# esp8285_v01.net
KiCad netlist of a schematic drawn in EAGLE
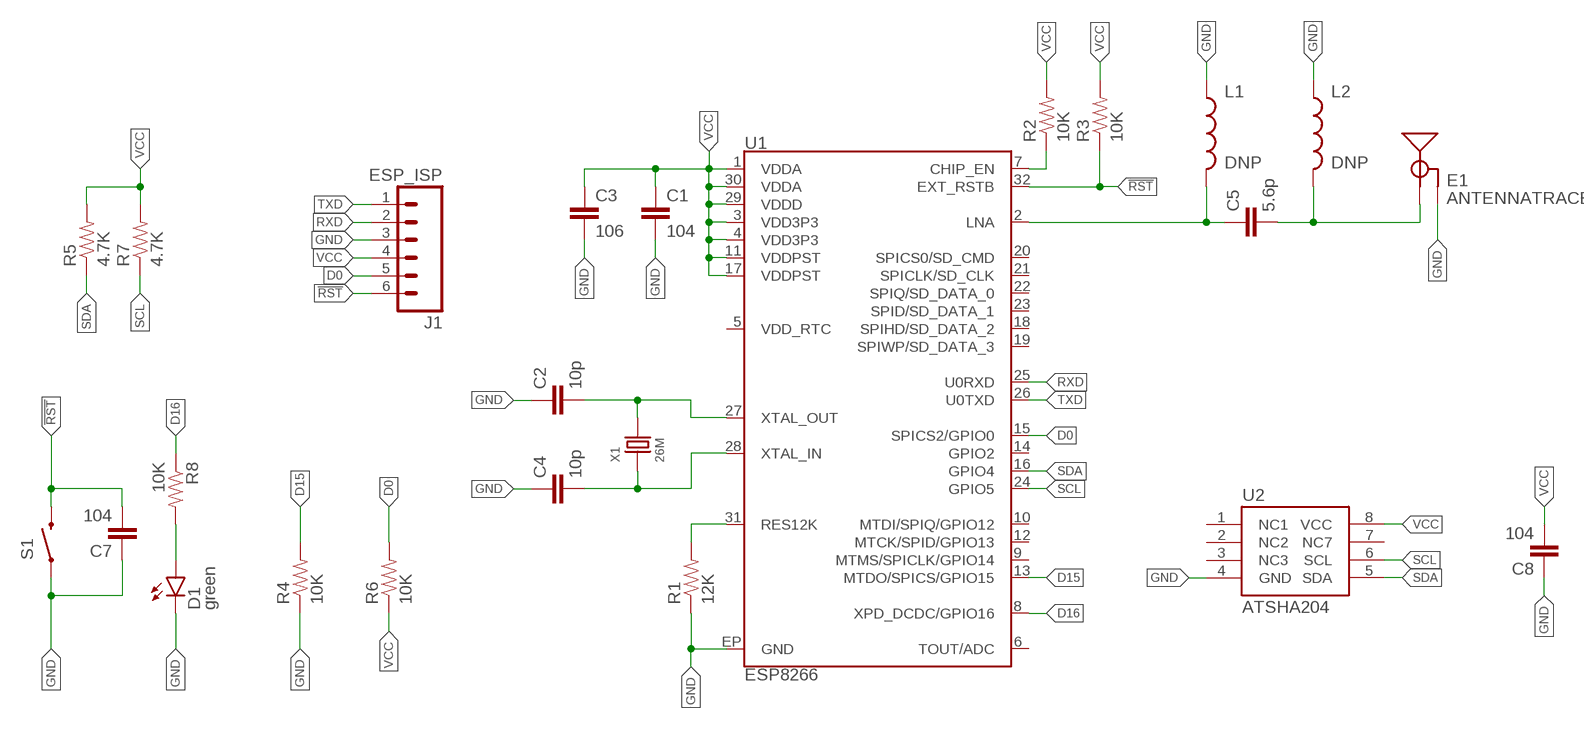
[diagram p0: schematic, sheet 1]

(export (version "E")
  (design (tool "Eeschema 10.0.6"))
  (components
    (comp (ref "C1")
      (value "104")
      (footprint "eagle-import:0402-CAP")
      (libsource (lib "eagle-import") (part "CAP0402-CAP"))
    )
    (comp (ref "C2")
      (value "10p")
      (footprint "eagle-import:0402-CAP")
      (libsource (lib "eagle-import") (part "CAP0402-CAP"))
    )
    (comp (ref "C3")
      (value "106")
      (footprint "eagle-import:0402-CAP")
      (libsource (lib "eagle-import") (part "CAP0402-CAP"))
    )
    (comp (ref "C4")
      (value "10p")
      (footprint "eagle-import:0402-CAP")
      (libsource (lib "eagle-import") (part "CAP0402-CAP"))
    )
    (comp (ref "C5")
      (value "5.6p")
      (footprint "eagle-import:0402-CAP")
      (libsource (lib "eagle-import") (part "CAP0402-CAP"))
    )
    (comp (ref "C7")
      (value "104")
      (footprint "eagle-import:0402-CAP")
      (libsource (lib "eagle-import") (part "CAP0402-CAP"))
    )
    (comp (ref "C8")
      (value "104")
      (footprint "eagle-import:0402-CAP")
      (libsource (lib "eagle-import") (part "CAP0402-CAP"))
    )
    (comp (ref "D1")
      (value "green")
      (footprint "eagle-import:LED-0603-EASY")
      (libsource (lib "eagle-import") (part "LED-EASY"))
    )
    (comp (ref "E1")
      (value "ANTENNATRACE")
      (footprint "eagle-import:TRACE_ANTENNA_2.4GHZ_25.7MM")
      (libsource (lib "eagle-import") (part "ANTENNATRACE"))
    )
    (comp (ref "J1")
      (value "ESP_ISP")
      (footprint "eagle-import:1X06_NO_SILK")
      (libsource (lib "eagle-import") (part "M06NO_SILK_FEMALE_PTH"))
    )
    (comp (ref "L1")
      (value "DNP")
      (footprint "eagle-import:C0402")
      (libsource (lib "eagle-import") (part "INDUCTOR0402"))
    )
    (comp (ref "L2")
      (value "DNP")
      (footprint "eagle-import:C0402")
      (libsource (lib "eagle-import") (part "INDUCTOR0402"))
    )
    (comp (ref "R1")
      (value "12K")
      (footprint "eagle-import:0402-RES")
      (libsource (lib "eagle-import") (part "RESISTOR0402"))
    )
    (comp (ref "R2")
      (value "10K")
      (footprint "eagle-import:0402-RES")
      (libsource (lib "eagle-import") (part "RESISTOR0402"))
    )
    (comp (ref "R3")
      (value "10K")
      (footprint "eagle-import:0402-RES")
      (libsource (lib "eagle-import") (part "RESISTOR0402"))
    )
    (comp (ref "R4")
      (value "10K")
      (footprint "eagle-import:0402-RES")
      (libsource (lib "eagle-import") (part "RESISTOR0402"))
    )
    (comp (ref "R5")
      (value "4.7K")
      (footprint "eagle-import:0402-RES")
      (libsource (lib "eagle-import") (part "RESISTOR0402"))
    )
    (comp (ref "R6")
      (value "10K")
      (footprint "eagle-import:0402-RES")
      (libsource (lib "eagle-import") (part "RESISTOR0402"))
    )
    (comp (ref "R7")
      (value "4.7K")
      (footprint "eagle-import:0402-RES")
      (libsource (lib "eagle-import") (part "RESISTOR0402"))
    )
    (comp (ref "R8")
      (value "10K")
      (footprint "eagle-import:0402-RES")
      (libsource (lib "eagle-import") (part "RESISTOR0402"))
    )
    (comp (ref "S1")
      (value "SWITCH-MOMENTARY-2SMD-1101NE")
      (footprint "eagle-import:TACTILE-SWITCH-1101NE")
      (libsource (lib "eagle-import") (part "SWITCH-MOMENTARY-2SMD-1101NE"))
    )
    (comp (ref "U1")
      (value "ESP8266")
      (footprint "eagle-import:QFN32")
      (libsource (lib "eagle-import") (part "ESP8266"))
    )
    (comp (ref "U2")
      (value "ATSHA204")
      (footprint "eagle-import:SO08")
      (libsource (lib "eagle-import") (part "ATSHA204_SOIC8"))
    )
    (comp (ref "X1")
      (value "26M")
      (footprint "eagle-import:X4-SMD-3.2X2.5X0.7MM")
      (libsource (lib "eagle-import") (part "CRYSTAL'3225'"))
    )
  )
  (nets
    (net (code "1") (name "/~{RST}") (class "Default")
      (node (ref "C7") (pin "2") (pinfunction "2_2") (pintype "passive"))
      (node (ref "J1") (pin "6") (pinfunction "6_6") (pintype "passive"))
      (node (ref "R3") (pin "1") (pinfunction "1_1") (pintype "passive"))
      (node (ref "S1") (pin "2") (pinfunction "2_2") (pintype "passive"))
      (node (ref "U1") (pin "32") (pinfunction "EXT_RSTB_32") (pintype "bidirectional"))
    )
    (net (code "2") (name "D0") (class "Default")
      (node (ref "J1") (pin "5") (pinfunction "5_5") (pintype "passive"))
      (node (ref "R6") (pin "2") (pinfunction "2_2") (pintype "passive"))
      (node (ref "U1") (pin "15") (pinfunction "SPICS2/GPIO0_15") (pintype "bidirectional"))
    )
    (net (code "3") (name "D15") (class "Default")
      (node (ref "R4") (pin "2") (pinfunction "2_2") (pintype "passive"))
      (node (ref "U1") (pin "13") (pinfunction "MTDO/SPICS/GPIO15_13") (pintype "bidirectional"))
    )
    (net (code "4") (name "D16") (class "Default")
      (node (ref "R8") (pin "1") (pinfunction "1_1") (pintype "passive"))
      (node (ref "U1") (pin "8") (pinfunction "XPD_DCDC/GPIO16_8") (pintype "bidirectional"))
    )
    (net (code "5") (name "GND") (class "Default")
      (node (ref "C1") (pin "2") (pinfunction "2_2") (pintype "passive"))
      (node (ref "C2") (pin "1") (pinfunction "1_1") (pintype "passive"))
      (node (ref "C3") (pin "2") (pinfunction "2_2") (pintype "passive"))
      (node (ref "C4") (pin "1") (pinfunction "1_1") (pintype "passive"))
      (node (ref "C7") (pin "1") (pinfunction "1_1") (pintype "passive"))
      (node (ref "C8") (pin "1") (pinfunction "1_1") (pintype "passive"))
      (node (ref "D1") (pin "-") (pinfunction "C_-") (pintype "passive"))
      (node (ref "E1") (pin "GND") (pinfunction "GND_GND") (pintype "bidirectional"))
      (node (ref "E1") (pin "GND2") (pinfunction "GND_GND2") (pintype "bidirectional"))
      (node (ref "J1") (pin "3") (pinfunction "3_3") (pintype "passive"))
      (node (ref "L1") (pin "1") (pinfunction "1_1") (pintype "passive"))
      (node (ref "L2") (pin "1") (pinfunction "1_1") (pintype "passive"))
      (node (ref "R1") (pin "1") (pinfunction "1_1") (pintype "passive"))
      (node (ref "R4") (pin "1") (pinfunction "1_1") (pintype "passive"))
      (node (ref "S1") (pin "1") (pinfunction "1_1") (pintype "passive"))
      (node (ref "U1") (pin "EP") (pinfunction "GND_EP") (pintype "bidirectional"))
      (node (ref "U2") (pin "4") (pinfunction "GND_4") (pintype "power_in"))
    )
    (net (code "6") (name "Net-(D1-A)") (class "Default")
      (node (ref "D1") (pin "+") (pinfunction "A_+") (pintype "passive"))
      (node (ref "R8") (pin "2") (pinfunction "2_2") (pintype "passive"))
    )
    (net (code "7") (name "Net-(E1-SIGNAL)") (class "Default")
      (node (ref "C5") (pin "2") (pinfunction "2_2") (pintype "passive"))
      (node (ref "E1") (pin "ANT") (pinfunction "SIGNAL_ANT") (pintype "bidirectional"))
      (node (ref "L2") (pin "2") (pinfunction "2_2") (pintype "passive"))
    )
    (net (code "8") (name "Net-(U1-CHIP_EN)") (class "Default")
      (node (ref "R2") (pin "1") (pinfunction "1_1") (pintype "passive"))
      (node (ref "U1") (pin "7") (pinfunction "CHIP_EN_7") (pintype "bidirectional"))
    )
    (net (code "9") (name "Net-(U1-LNA)") (class "Default")
      (node (ref "C5") (pin "1") (pinfunction "1_1") (pintype "passive"))
      (node (ref "L1") (pin "2") (pinfunction "2_2") (pintype "passive"))
      (node (ref "U1") (pin "2") (pinfunction "LNA_2") (pintype "bidirectional"))
    )
    (net (code "10") (name "Net-(U1-RES12K)") (class "Default")
      (node (ref "R1") (pin "2") (pinfunction "2_2") (pintype "passive"))
      (node (ref "U1") (pin "31") (pinfunction "RES12K_31") (pintype "bidirectional"))
    )
    (net (code "11") (name "Net-(U1-XTAL_IN)") (class "Default")
      (node (ref "C4") (pin "2") (pinfunction "2_2") (pintype "passive"))
      (node (ref "U1") (pin "28") (pinfunction "XTAL_IN_28") (pintype "bidirectional"))
      (node (ref "X1") (pin "1") (pinfunction "1_1") (pintype "passive"))
    )
    (net (code "12") (name "Net-(U1-XTAL_OUT)") (class "Default")
      (node (ref "C2") (pin "2") (pinfunction "2_2") (pintype "passive"))
      (node (ref "U1") (pin "27") (pinfunction "XTAL_OUT_27") (pintype "bidirectional"))
      (node (ref "X1") (pin "3") (pinfunction "2_3") (pintype "passive"))
    )
    (net (code "13") (name "RXD") (class "Default")
      (node (ref "J1") (pin "2") (pinfunction "2_2") (pintype "passive"))
      (node (ref "U1") (pin "25") (pinfunction "U0RXD_25") (pintype "bidirectional"))
    )
    (net (code "14") (name "SCL") (class "Default")
      (node (ref "R7") (pin "1") (pinfunction "1_1") (pintype "passive"))
      (node (ref "U1") (pin "24") (pinfunction "GPIO5_24") (pintype "bidirectional"))
      (node (ref "U2") (pin "6") (pinfunction "SCL_6") (pintype "bidirectional"))
    )
    (net (code "15") (name "SDA") (class "Default")
      (node (ref "R5") (pin "1") (pinfunction "1_1") (pintype "passive"))
      (node (ref "U1") (pin "16") (pinfunction "GPIO4_16") (pintype "bidirectional"))
      (node (ref "U2") (pin "5") (pinfunction "SDA_5") (pintype "bidirectional"))
    )
    (net (code "16") (name "TXD") (class "Default")
      (node (ref "J1") (pin "1") (pinfunction "1_1") (pintype "passive"))
      (node (ref "U1") (pin "26") (pinfunction "U0TXD_26") (pintype "bidirectional"))
    )
    (net (code "17") (name "VCC") (class "Default")
      (node (ref "C1") (pin "1") (pinfunction "1_1") (pintype "passive"))
      (node (ref "C3") (pin "1") (pinfunction "1_1") (pintype "passive"))
      (node (ref "C8") (pin "2") (pinfunction "2_2") (pintype "passive"))
      (node (ref "J1") (pin "4") (pinfunction "4_4") (pintype "passive"))
      (node (ref "R2") (pin "2") (pinfunction "2_2") (pintype "passive"))
      (node (ref "R3") (pin "2") (pinfunction "2_2") (pintype "passive"))
      (node (ref "R5") (pin "2") (pinfunction "2_2") (pintype "passive"))
      (node (ref "R6") (pin "1") (pinfunction "1_1") (pintype "passive"))
      (node (ref "R7") (pin "2") (pinfunction "2_2") (pintype "passive"))
      (node (ref "U1") (pin "1") (pinfunction "VDDA_1") (pintype "bidirectional"))
      (node (ref "U1") (pin "11") (pinfunction "VDDPST_11") (pintype "bidirectional"))
      (node (ref "U1") (pin "17") (pinfunction "VDDPST_17") (pintype "bidirectional"))
      (node (ref "U1") (pin "29") (pinfunction "VDDD_29") (pintype "bidirectional"))
      (node (ref "U1") (pin "3") (pinfunction "VDD3P3_3") (pintype "bidirectional"))
      (node (ref "U1") (pin "30") (pinfunction "VDDA_30") (pintype "bidirectional"))
      (node (ref "U1") (pin "4") (pinfunction "VDD3P3_4") (pintype "bidirectional"))
      (node (ref "U2") (pin "8") (pinfunction "VCC_8") (pintype "power_in"))
    )
    (net (code "18") (name "unconnected-(U1-GPIO2-Pad14)") (class "Default")
      (node (ref "U1") (pin "14") (pinfunction "GPIO2_14") (pintype "bidirectional"))
    )
    (net (code "19") (name "unconnected-(U1-MTCK{slash}SPID{slash}GPIO13-Pad12)") (class "Default")
      (node (ref "U1") (pin "12") (pinfunction "MTCK/SPID/GPIO13_12") (pintype "bidirectional"))
    )
    (net (code "20") (name "unconnected-(U1-MTDI{slash}SPIQ{slash}GPIO12-Pad10)") (class "Default")
      (node (ref "U1") (pin "10") (pinfunction "MTDI/SPIQ/GPIO12_10") (pintype "bidirectional"))
    )
    (net (code "21") (name "unconnected-(U1-MTMS{slash}SPICLK{slash}GPIO14-Pad9)") (class "Default")
      (node (ref "U1") (pin "9") (pinfunction "MTMS/SPICLK/GPIO14_9") (pintype "bidirectional"))
    )
    (net (code "22") (name "unconnected-(U1-SPICLK{slash}SD_CLK-Pad21)") (class "Default")
      (node (ref "U1") (pin "21") (pinfunction "SPICLK/SD_CLK_21") (pintype "bidirectional"))
    )
    (net (code "23") (name "unconnected-(U1-SPICS0{slash}SD_CMD-Pad20)") (class "Default")
      (node (ref "U1") (pin "20") (pinfunction "SPICS0/SD_CMD_20") (pintype "bidirectional"))
    )
    (net (code "24") (name "unconnected-(U1-SPID{slash}SD_DATA_1-Pad23)") (class "Default")
      (node (ref "U1") (pin "23") (pinfunction "SPID/SD_DATA_1_23") (pintype "bidirectional"))
    )
    (net (code "25") (name "unconnected-(U1-SPIHD{slash}SD_DATA_2-Pad18)") (class "Default")
      (node (ref "U1") (pin "18") (pinfunction "SPIHD/SD_DATA_2_18") (pintype "bidirectional"))
    )
    (net (code "26") (name "unconnected-(U1-SPIQ{slash}SD_DATA_0-Pad22)") (class "Default")
      (node (ref "U1") (pin "22") (pinfunction "SPIQ/SD_DATA_0_22") (pintype "bidirectional"))
    )
    (net (code "27") (name "unconnected-(U1-SPIWP{slash}SD_DATA_3-Pad19)") (class "Default")
      (node (ref "U1") (pin "19") (pinfunction "SPIWP/SD_DATA_3_19") (pintype "bidirectional"))
    )
    (net (code "28") (name "unconnected-(U1-TOUT{slash}ADC-Pad6)") (class "Default")
      (node (ref "U1") (pin "6") (pinfunction "TOUT/ADC_6") (pintype "bidirectional"))
    )
    (net (code "29") (name "unconnected-(U1-VDD_RTC-Pad5)") (class "Default")
      (node (ref "U1") (pin "5") (pinfunction "VDD_RTC_5") (pintype "bidirectional"))
    )
    (net (code "30") (name "unconnected-(U2-NC1-Pad1)") (class "Default")
      (node (ref "U2") (pin "1") (pinfunction "NC1_1") (pintype "no_connect"))
    )
    (net (code "31") (name "unconnected-(U2-NC2-Pad2)") (class "Default")
      (node (ref "U2") (pin "2") (pinfunction "NC2_2") (pintype "no_connect"))
    )
    (net (code "32") (name "unconnected-(U2-NC3-Pad3)") (class "Default")
      (node (ref "U2") (pin "3") (pinfunction "NC3_3") (pintype "no_connect"))
    )
    (net (code "33") (name "unconnected-(U2-NC7-Pad7)") (class "Default")
      (node (ref "U2") (pin "7") (pinfunction "NC7_7") (pintype "no_connect"))
    )
  )
)
